# aircraft.net
KiCad netlist of a schematic drawn in Altium Designer
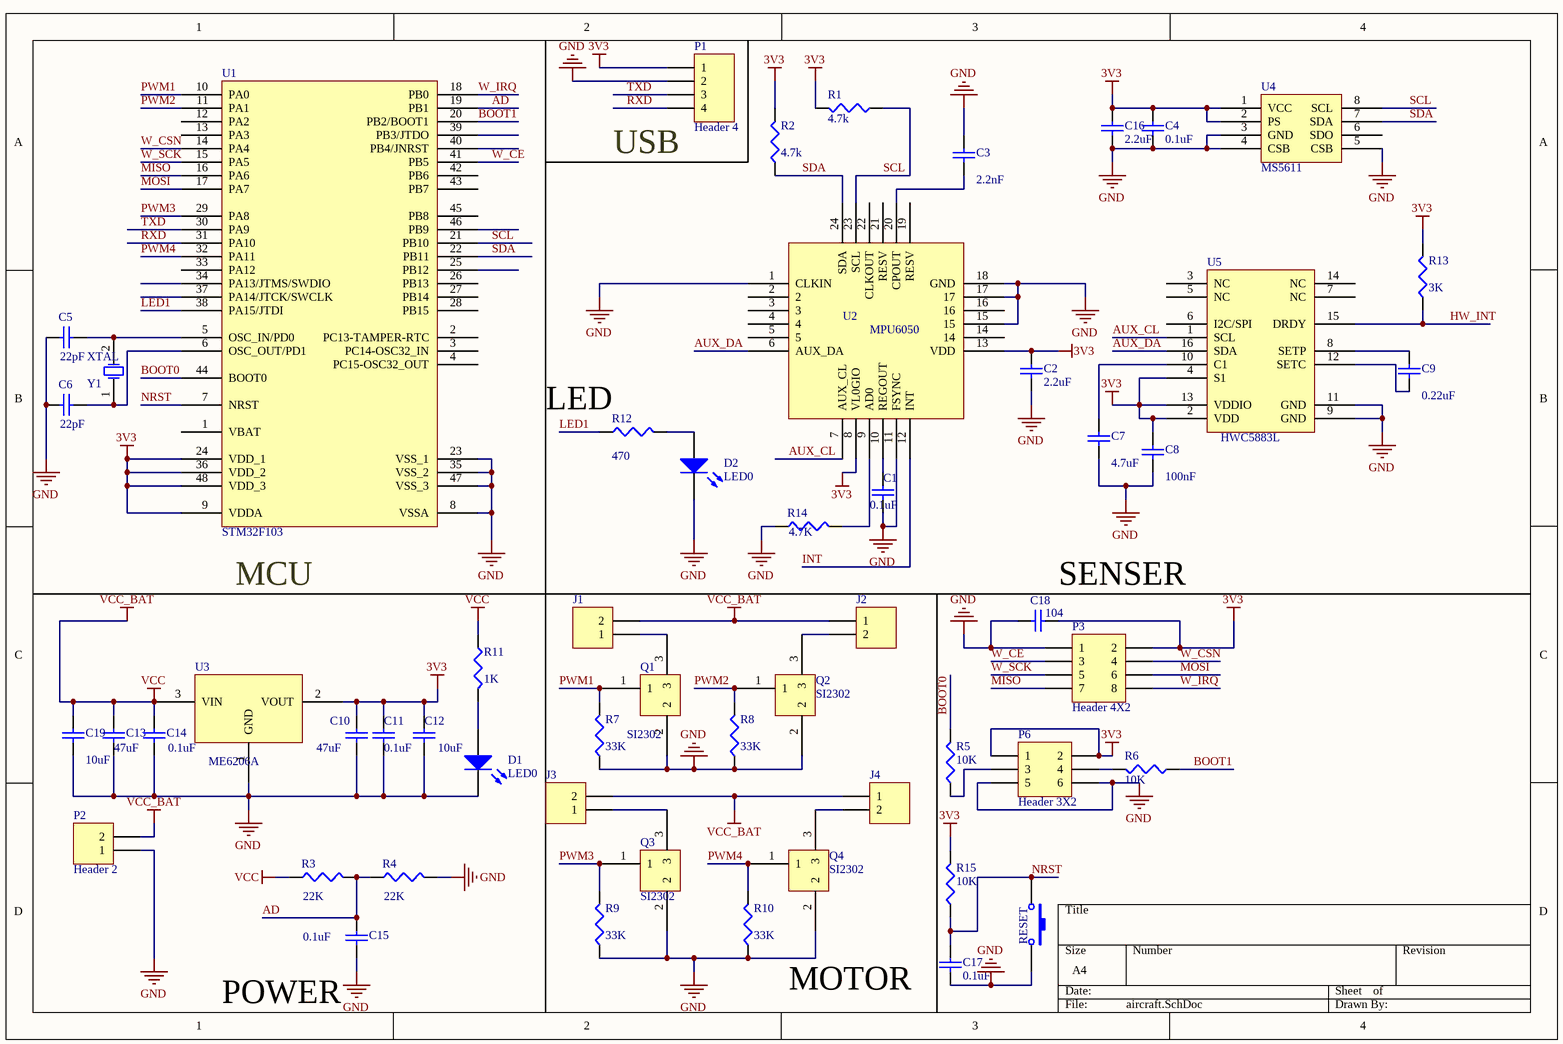
[diagram p0: aircraft.SchDoc]

(export (version "E")
  (design (tool "Eeschema 10.0.6"))
  (components
    (comp (ref "C1")
      (value "0.1uF")
      (footprint "0402")
      (description "Capacitor")
      (fields (field (name "Comment") "Cap") (field (name "PUBLISHER") "Altium Limited"))
      (libsource (lib "Miscellaneous Devices") (part "Cap"))
    )
    (comp (ref "C2")
      (value "2.2uF")
      (footprint "0402")
      (description "Capacitor")
      (fields (field (name "Comment") "Cap") (field (name "PUBLISHER") "Altium Limited"))
      (libsource (lib "Miscellaneous Devices") (part "Cap"))
    )
    (comp (ref "C3")
      (value "2.2nF")
      (footprint "0402")
      (description "Capacitor")
      (fields (field (name "Comment") "Cap") (field (name "PUBLISHER") "Altium Limited"))
      (libsource (lib "Miscellaneous Devices") (part "Cap"))
    )
    (comp (ref "C4")
      (value "0.1uF")
      (footprint "0402")
      (description "Capacitor")
      (fields (field (name "Comment") "Cap") (field (name "PUBLISHER") "Altium Limited"))
      (libsource (lib "Miscellaneous Devices") (part "Cap"))
    )
    (comp (ref "C5")
      (value "22pF")
      (footprint "0402")
      (description "Capacitor")
      (fields (field (name "Comment") "Cap") (field (name "PUBLISHER") "Altium Limited"))
      (libsource (lib "Miscellaneous Devices") (part "Cap"))
    )
    (comp (ref "C6")
      (value "22pF")
      (footprint "0402")
      (description "Capacitor")
      (fields (field (name "Comment") "Cap") (field (name "PUBLISHER") "Altium Limited"))
      (libsource (lib "Miscellaneous Devices") (part "Cap"))
    )
    (comp (ref "C7")
      (value "4.7uF")
      (footprint "0402")
      (description "Capacitor")
      (fields (field (name "Comment") "Cap") (field (name "PUBLISHER") "Altium Limited"))
      (libsource (lib "Miscellaneous Devices") (part "Cap"))
    )
    (comp (ref "C8")
      (value "100nF")
      (footprint "0402")
      (description "Capacitor")
      (fields (field (name "Comment") "Cap") (field (name "PUBLISHER") "Altium Limited"))
      (libsource (lib "Miscellaneous Devices") (part "Cap"))
    )
    (comp (ref "C9")
      (value "0.22uF")
      (footprint "0402")
      (description "Capacitor")
      (fields (field (name "Comment") "Cap") (field (name "PUBLISHER") "Altium Limited"))
      (libsource (lib "Miscellaneous Devices") (part "Cap"))
    )
    (comp (ref "C10")
      (value "47uF")
      (footprint "6-0805_L")
      (description "Capacitor")
      (fields (field (name "Comment") "Cap") (field (name "PUBLISHER") "Altium Limited"))
      (libsource (lib "Miscellaneous Devices") (part "Cap"))
    )
    (comp (ref "C11")
      (value "0.1uF")
      (footprint "0402")
      (description "Capacitor")
      (fields (field (name "Comment") "Cap") (field (name "PUBLISHER") "Altium Limited"))
      (libsource (lib "Miscellaneous Devices") (part "Cap"))
    )
    (comp (ref "C12")
      (value "10uF")
      (footprint "1608[0603]")
      (description "Capacitor")
      (fields (field (name "Comment") "Cap") (field (name "PUBLISHER") "Altium Limited"))
      (libsource (lib "Miscellaneous Devices") (part "Cap"))
    )
    (comp (ref "C13")
      (value "47uF")
      (footprint "6-0805_L")
      (description "Capacitor")
      (fields (field (name "Comment") "Cap") (field (name "PUBLISHER") "Altium Limited"))
      (libsource (lib "Miscellaneous Devices") (part "Cap"))
    )
    (comp (ref "C14")
      (value "0.1uF")
      (footprint "0402")
      (description "Capacitor")
      (fields (field (name "Comment") "Cap") (field (name "PUBLISHER") "Altium Limited"))
      (libsource (lib "Miscellaneous Devices") (part "Cap"))
    )
    (comp (ref "C15")
      (value "0.1uF")
      (footprint "0402")
      (description "Capacitor")
      (fields (field (name "Comment") "Cap") (field (name "PUBLISHER") "Altium Limited"))
      (libsource (lib "Miscellaneous Devices") (part "Cap"))
    )
    (comp (ref "C16")
      (value "2.2uF")
      (footprint "0402")
      (description "Capacitor")
      (fields (field (name "Comment") "Cap") (field (name "PUBLISHER") "Altium Limited"))
      (libsource (lib "Miscellaneous Devices") (part "Cap"))
    )
    (comp (ref "C17")
      (value "0.1uF")
      (footprint "0402")
      (description "Capacitor")
      (fields (field (name "Comment") "Cap") (field (name "PUBLISHER") "Altium Limited"))
      (libsource (lib "Miscellaneous Devices") (part "Cap"))
    )
    (comp (ref "C18")
      (value "104")
      (footprint "0402")
      (description "Capacitor")
      (fields (field (name "Comment") "Cap") (field (name "PUBLISHER") "Altium Limited"))
      (libsource (lib "Miscellaneous Devices") (part "Cap"))
    )
    (comp (ref "C19")
      (value "10uF")
      (footprint "1608[0603]")
      (description "Capacitor")
      (fields (field (name "Comment") "Cap") (field (name "PUBLISHER") "Altium Limited"))
      (libsource (lib "Miscellaneous Devices") (part "Cap"))
    )
    (comp (ref "D1")
      (value "LED0")
      (footprint "1608[0603]")
      (description "Typical INFRARED GaAs LED")
      (fields (field (name "PUBLISHER") "Altium Limited"))
      (libsource (lib "Miscellaneous Devices") (part "LED0"))
    )
    (comp (ref "D2")
      (value "LED0")
      (footprint "1608[0603]")
      (description "Typical INFRARED GaAs LED")
      (fields (field (name "PUBLISHER") "Altium Limited"))
      (libsource (lib "Miscellaneous Devices") (part "LED0"))
    )
    (comp (ref "J1")
      (value "Header 2")
      (footprint "HDR1X2")
      (description "Header, 2-Pin")
      (fields (field (name "PUBLISHER") "Altium Limited"))
      (libsource (lib "Miscellaneous Connectors") (part "Header 2"))
    )
    (comp (ref "J2")
      (value "Header 2")
      (footprint "HDR1X2")
      (description "Header, 2-Pin")
      (fields (field (name "PUBLISHER") "Altium Limited"))
      (libsource (lib "") (part "Header 2_1"))
    )
    (comp (ref "J3")
      (value "Header 2")
      (footprint "HDR1X2")
      (description "Header, 2-Pin")
      (fields (field (name "PUBLISHER") "Altium Limited"))
      (libsource (lib "Miscellaneous Connectors") (part "Header 2"))
    )
    (comp (ref "J4")
      (value "Header 2")
      (footprint "HDR1X2")
      (description "Header, 2-Pin")
      (fields (field (name "PUBLISHER") "Altium Limited"))
      (libsource (lib "") (part "Header 2_1"))
    )
    (comp (ref "P1")
      (value "Header 4")
      (footprint "HDR1X4")
      (description "Header, 4-Pin")
      (fields (field (name "PUBLISHER") "Altium Limited"))
      (libsource (lib "Miscellaneous Connectors") (part "Header 4"))
    )
    (comp (ref "P2")
      (value "Header 2")
      (footprint "HDR1X2")
      (description "Header, 2-Pin")
      (fields (field (name "PUBLISHER") "Altium Limited"))
      (libsource (lib "Miscellaneous Connectors") (part "Header 2"))
    )
    (comp (ref "P3")
      (value "Header 4X2")
      (footprint "HDR2X4")
      (description "Header, 4-Pin, Dual row")
      (fields (field (name "PUBLISHER") "Altium Limited"))
      (libsource (lib "Miscellaneous Connectors") (part "Header 4X2"))
    )
    (comp (ref "P6")
      (value "Header 3X2")
      (footprint "HDR2X3")
      (description "Header, 3-Pin, Dual row")
      (fields (field (name "PUBLISHER") "Altium Limited"))
      (libsource (lib "Miscellaneous Connectors") (part "Header 3X2"))
    )
    (comp (ref "Q1")
      (value "SI2302")
      (footprint "SOT-23_M")
      (libsource (lib "aircraftschlib") (part "SI2302"))
    )
    (comp (ref "Q2")
      (value "SI2302")
      (footprint "SOT-23_M")
      (libsource (lib "aircraftschlib") (part "SI2302"))
    )
    (comp (ref "Q3")
      (value "SI2302")
      (footprint "SOT-23_M")
      (libsource (lib "aircraftschlib") (part "SI2302"))
    )
    (comp (ref "Q4")
      (value "SI2302")
      (footprint "SOT-23_M")
      (libsource (lib "aircraftschlib") (part "SI2302"))
    )
    (comp (ref "R1")
      (value "4.7k")
      (footprint "0402")
      (description "Resistor")
      (fields (field (name "Comment") "Res3") (field (name "PUBLISHER") "Altium Limited"))
      (libsource (lib "Miscellaneous Devices") (part "Res3"))
    )
    (comp (ref "R2")
      (value "4.7k")
      (footprint "0402")
      (description "Resistor")
      (fields (field (name "Comment") "Res3") (field (name "PUBLISHER") "Altium Limited"))
      (libsource (lib "Miscellaneous Devices") (part "Res3"))
    )
    (comp (ref "R3")
      (value "22K")
      (footprint "0402")
      (description "Resistor")
      (fields (field (name "Comment") "Res3") (field (name "PUBLISHER") "Altium Limited"))
      (libsource (lib "Miscellaneous Devices") (part "Res3"))
    )
    (comp (ref "R4")
      (value "22K")
      (footprint "0402")
      (description "Resistor")
      (fields (field (name "Comment") "Res3") (field (name "PUBLISHER") "Altium Limited"))
      (libsource (lib "Miscellaneous Devices") (part "Res3"))
    )
    (comp (ref "R5")
      (value "10K")
      (footprint "0402")
      (description "Resistor")
      (fields (field (name "Comment") "Res3") (field (name "PUBLISHER") "Altium Limited"))
      (libsource (lib "Miscellaneous Devices") (part "Res3"))
    )
    (comp (ref "R6")
      (value "10K")
      (footprint "0402")
      (description "Resistor")
      (fields (field (name "Comment") "Res3") (field (name "PUBLISHER") "Altium Limited"))
      (libsource (lib "Miscellaneous Devices") (part "Res3"))
    )
    (comp (ref "R7")
      (value "33K")
      (footprint "0402")
      (description "Resistor")
      (fields (field (name "Comment") "Res3") (field (name "PUBLISHER") "Altium Limited"))
      (libsource (lib "Miscellaneous Devices") (part "Res3"))
    )
    (comp (ref "R8")
      (value "33K")
      (footprint "0402")
      (description "Resistor")
      (fields (field (name "Comment") "Res3") (field (name "PUBLISHER") "Altium Limited"))
      (libsource (lib "Miscellaneous Devices") (part "Res3"))
    )
    (comp (ref "R9")
      (value "33K")
      (footprint "0402")
      (description "Resistor")
      (fields (field (name "Comment") "Res3") (field (name "PUBLISHER") "Altium Limited"))
      (libsource (lib "Miscellaneous Devices") (part "Res3"))
    )
    (comp (ref "R10")
      (value "33K")
      (footprint "0402")
      (description "Resistor")
      (fields (field (name "Comment") "Res3") (field (name "PUBLISHER") "Altium Limited"))
      (libsource (lib "Miscellaneous Devices") (part "Res3"))
    )
    (comp (ref "R11")
      (value "1K")
      (footprint "0402")
      (description "Resistor")
      (fields (field (name "Comment") "Res3") (field (name "PUBLISHER") "Altium Limited"))
      (libsource (lib "Miscellaneous Devices") (part "Res3"))
    )
    (comp (ref "R12")
      (value "470")
      (footprint "0402")
      (description "Resistor")
      (fields (field (name "Comment") "Res3") (field (name "PUBLISHER") "Altium Limited"))
      (libsource (lib "Miscellaneous Devices") (part "Res3"))
    )
    (comp (ref "R13")
      (value "3K")
      (footprint "0402")
      (description "Resistor")
      (fields (field (name "Comment") "Res3") (field (name "PUBLISHER") "Altium Limited"))
      (libsource (lib "Miscellaneous Devices") (part "Res3"))
    )
    (comp (ref "R14")
      (value "4.7K")
      (footprint "0402")
      (description "Resistor")
      (fields (field (name "Comment") "Res3") (field (name "PUBLISHER") "Altium Limited"))
      (libsource (lib "Miscellaneous Devices") (part "Res3"))
    )
    (comp (ref "R15")
      (value "10K")
      (footprint "0402")
      (description "Resistor")
      (fields (field (name "Comment") "Res3") (field (name "PUBLISHER") "Altium Limited"))
      (libsource (lib "Miscellaneous Devices") (part "Res3"))
    )
    (comp (ref "RESET")
      (value "SW-PB")
      (footprint "SW2")
      (description "Switch")
      (fields (field (name "PUBLISHER") "Altium Limited"))
      (libsource (lib "Miscellaneous Devices") (part "SW-PB"))
    )
    (comp (ref "U1")
      (value "STM32F103")
      (footprint "LQFP48S")
      (libsource (lib "aircraftschlib") (part "STM32F103"))
    )
    (comp (ref "U2")
      (value "MPU6050")
      (footprint "QFN24")
      (libsource (lib "aircraftschlib") (part "MPU6050"))
    )
    (comp (ref "U3")
      (value "ME6206A")
      (footprint "SOT23_M")
      (libsource (lib "aircraftschlib") (part "ME6206A"))
    )
    (comp (ref "U4")
      (value "MS5611")
      (footprint "MS5611 - duplicate")
      (libsource (lib "aircraftschlib") (part "MS5611"))
    )
    (comp (ref "U5")
      (value "HWC5883L")
      (footprint "HMC5883L")
      (libsource (lib "aircraftschlib") (part "HMC5883L"))
    )
    (comp (ref "Y1")
      (value "XTAL")
      (footprint "XTAL2")
      (description "Crystal Oscillator")
      (fields (field (name "PUBLISHER") "Altium Limited"))
      (libsource (lib "Miscellaneous Devices") (part "XTAL"))
    )
  )
  (nets
    (net (code "1") (name "/AD") (class "Default")
      (node (ref "C15") (pin "2") (pinfunction "2_2") (pintype "passive"))
      (node (ref "R3") (pin "2") (pinfunction "2_2") (pintype "passive"))
      (node (ref "R4") (pin "1") (pinfunction "1_1") (pintype "passive"))
      (node (ref "U1") (pin "19") (pinfunction "PB1_19") (pintype "passive"))
    )
    (net (code "2") (name "/AUX_CL") (class "Default")
      (node (ref "U2") (pin "7") (pinfunction "AUX_CL_7") (pintype "passive"))
      (node (ref "U5") (pin "1") (pinfunction "SCL_1") (pintype "passive"))
    )
    (net (code "3") (name "/AUX_DA") (class "Default")
      (node (ref "U2") (pin "6") (pinfunction "AUX_DA_6") (pintype "passive"))
      (node (ref "U5") (pin "16") (pinfunction "SDA_16") (pintype "passive"))
    )
    (net (code "4") (name "/BOOT0") (class "Default")
      (node (ref "R5") (pin "2") (pinfunction "2_2") (pintype "passive"))
      (node (ref "U1") (pin "44") (pinfunction "BOOT0_44") (pintype "passive"))
    )
    (net (code "5") (name "/BOOT1") (class "Default")
      (node (ref "R6") (pin "1") (pinfunction "1_1") (pintype "passive"))
      (node (ref "U1") (pin "20") (pinfunction "PB2/BOOT1_20") (pintype "passive"))
    )
    (net (code "6") (name "/HW_INT") (class "Default")
      (node (ref "R13") (pin "1") (pinfunction "1_1") (pintype "passive"))
      (node (ref "U5") (pin "15") (pinfunction "DRDY_15") (pintype "passive"))
    )
    (net (code "7") (name "/INT") (class "Default")
      (node (ref "U2") (pin "12") (pinfunction "INT_12") (pintype "passive"))
    )
    (net (code "8") (name "/LED1") (class "Default")
      (node (ref "R12") (pin "1") (pinfunction "1_1") (pintype "passive"))
      (node (ref "U1") (pin "38") (pinfunction "PA15/JTDI_38") (pintype "passive"))
    )
    (net (code "9") (name "/MISO") (class "Default")
      (node (ref "P3") (pin "7") (pinfunction "7_7") (pintype "passive"))
      (node (ref "U1") (pin "16") (pinfunction "PA6_16") (pintype "passive"))
    )
    (net (code "10") (name "/MOSI") (class "Default")
      (node (ref "P3") (pin "6") (pinfunction "6_6") (pintype "passive"))
      (node (ref "U1") (pin "17") (pinfunction "PA7_17") (pintype "passive"))
    )
    (net (code "11") (name "/NRST") (class "Default")
      (node (ref "C17") (pin "1") (pinfunction "1_1") (pintype "passive"))
      (node (ref "R15") (pin "1") (pinfunction "1_1") (pintype "passive"))
      (node (ref "RESET") (pin "1") (pinfunction "1_1") (pintype "passive"))
      (node (ref "U1") (pin "7") (pinfunction "NRST_7") (pintype "passive"))
    )
    (net (code "12") (name "/PWM1") (class "Default")
      (node (ref "Q1") (pin "1") (pinfunction "1_1") (pintype "passive"))
      (node (ref "R7") (pin "2") (pinfunction "2_2") (pintype "passive"))
      (node (ref "U1") (pin "10") (pinfunction "PA0_10") (pintype "passive"))
    )
    (net (code "13") (name "/PWM2") (class "Default")
      (node (ref "Q2") (pin "1") (pinfunction "1_1") (pintype "passive"))
      (node (ref "R8") (pin "2") (pinfunction "2_2") (pintype "passive"))
      (node (ref "U1") (pin "11") (pinfunction "PA1_11") (pintype "passive"))
    )
    (net (code "14") (name "/PWM3") (class "Default")
      (node (ref "Q3") (pin "1") (pinfunction "1_1") (pintype "passive"))
      (node (ref "R9") (pin "2") (pinfunction "2_2") (pintype "passive"))
      (node (ref "U1") (pin "29") (pinfunction "PA8_29") (pintype "passive"))
    )
    (net (code "15") (name "/PWM4") (class "Default")
      (node (ref "Q4") (pin "1") (pinfunction "1_1") (pintype "passive"))
      (node (ref "R10") (pin "2") (pinfunction "2_2") (pintype "passive"))
      (node (ref "U1") (pin "32") (pinfunction "PA11_32") (pintype "passive"))
    )
    (net (code "16") (name "/RXD") (class "Default")
      (node (ref "P1") (pin "4") (pinfunction "4_4") (pintype "passive"))
      (node (ref "U1") (pin "31") (pinfunction "PA10_31") (pintype "passive"))
    )
    (net (code "17") (name "/SCL") (class "Default")
      (node (ref "R1") (pin "1") (pinfunction "1_1") (pintype "passive"))
      (node (ref "U1") (pin "21") (pinfunction "PB10_21") (pintype "passive"))
      (node (ref "U2") (pin "23") (pinfunction "SCL_23") (pintype "passive"))
      (node (ref "U4") (pin "8") (pinfunction "SCL_8") (pintype "passive"))
    )
    (net (code "18") (name "/SDA") (class "Default")
      (node (ref "R2") (pin "1") (pinfunction "1_1") (pintype "passive"))
      (node (ref "U1") (pin "22") (pinfunction "PB11_22") (pintype "passive"))
      (node (ref "U2") (pin "24") (pinfunction "SDA_24") (pintype "passive"))
      (node (ref "U4") (pin "7") (pinfunction "SDA_7") (pintype "passive"))
    )
    (net (code "19") (name "/TXD") (class "Default")
      (node (ref "P1") (pin "3") (pinfunction "3_3") (pintype "passive"))
      (node (ref "U1") (pin "30") (pinfunction "PA9_30") (pintype "passive"))
    )
    (net (code "20") (name "/W_CE") (class "Default")
      (node (ref "P3") (pin "3") (pinfunction "3_3") (pintype "passive"))
      (node (ref "U1") (pin "41") (pinfunction "PB5_41") (pintype "passive"))
    )
    (net (code "21") (name "/W_CSN") (class "Default")
      (node (ref "P3") (pin "4") (pinfunction "4_4") (pintype "passive"))
      (node (ref "U1") (pin "14") (pinfunction "PA4_14") (pintype "passive"))
    )
    (net (code "22") (name "/W_IRQ") (class "Default")
      (node (ref "P3") (pin "8") (pinfunction "8_8") (pintype "passive"))
      (node (ref "U1") (pin "18") (pinfunction "PB0_18") (pintype "passive"))
    )
    (net (code "23") (name "/W_SCK") (class "Default")
      (node (ref "P3") (pin "5") (pinfunction "5_5") (pintype "passive"))
      (node (ref "U1") (pin "15") (pinfunction "PA5_15") (pintype "passive"))
    )
    (net (code "24") (name "3V3") (class "Default")
      (node (ref "C10") (pin "2") (pinfunction "2_2") (pintype "passive"))
      (node (ref "C11") (pin "1") (pinfunction "1_1") (pintype "passive"))
      (node (ref "C12") (pin "1") (pinfunction "1_1") (pintype "passive"))
      (node (ref "C16") (pin "2") (pinfunction "2_2") (pintype "passive"))
      (node (ref "C18") (pin "2") (pinfunction "2_2") (pintype "passive"))
      (node (ref "C2") (pin "2") (pinfunction "2_2") (pintype "passive"))
      (node (ref "C4") (pin "2") (pinfunction "2_2") (pintype "passive"))
      (node (ref "C8") (pin "2") (pinfunction "2_2") (pintype "passive"))
      (node (ref "P1") (pin "1") (pinfunction "1_1") (pintype "passive"))
      (node (ref "P3") (pin "2") (pinfunction "2_2") (pintype "passive"))
      (node (ref "P6") (pin "1") (pinfunction "1_1") (pintype "passive"))
      (node (ref "P6") (pin "2") (pinfunction "2_2") (pintype "passive"))
      (node (ref "R1") (pin "2") (pinfunction "2_2") (pintype "passive"))
      (node (ref "R13") (pin "2") (pinfunction "2_2") (pintype "passive"))
      (node (ref "R15") (pin "2") (pinfunction "2_2") (pintype "passive"))
      (node (ref "R2") (pin "2") (pinfunction "2_2") (pintype "passive"))
      (node (ref "U1") (pin "24") (pinfunction "VDD_1_24") (pintype "passive"))
      (node (ref "U1") (pin "36") (pinfunction "VDD_2_36") (pintype "passive"))
      (node (ref "U1") (pin "48") (pinfunction "VDD_3_48") (pintype "passive"))
      (node (ref "U1") (pin "9") (pinfunction "VDDA_9") (pintype "passive"))
      (node (ref "U2") (pin "13") (pinfunction "VDD_13") (pintype "passive"))
      (node (ref "U2") (pin "8") (pinfunction "VL0GIO_8") (pintype "passive"))
      (node (ref "U3") (pin "2") (pinfunction "VOUT_2") (pintype "passive"))
      (node (ref "U4") (pin "1") (pinfunction "VCC_1") (pintype "passive"))
      (node (ref "U4") (pin "2") (pinfunction "PS_2") (pintype "passive"))
      (node (ref "U5") (pin "13") (pinfunction "VDDIO_13") (pintype "passive"))
      (node (ref "U5") (pin "2") (pinfunction "VDD_2") (pintype "passive"))
      (node (ref "U5") (pin "4") (pinfunction "S1_4") (pintype "passive"))
    )
    (net (code "25") (name "GND") (class "Default")
      (node (ref "C1") (pin "1") (pinfunction "1_1") (pintype "passive"))
      (node (ref "C10") (pin "1") (pinfunction "1_1") (pintype "passive"))
      (node (ref "C11") (pin "2") (pinfunction "2_2") (pintype "passive"))
      (node (ref "C12") (pin "2") (pinfunction "2_2") (pintype "passive"))
      (node (ref "C13") (pin "1") (pinfunction "1_1") (pintype "passive"))
      (node (ref "C14") (pin "1") (pinfunction "1_1") (pintype "passive"))
      (node (ref "C15") (pin "1") (pinfunction "1_1") (pintype "passive"))
      (node (ref "C16") (pin "1") (pinfunction "1_1") (pintype "passive"))
      (node (ref "C17") (pin "2") (pinfunction "2_2") (pintype "passive"))
      (node (ref "C18") (pin "1") (pinfunction "1_1") (pintype "passive"))
      (node (ref "C19") (pin "1") (pinfunction "1_1") (pintype "passive"))
      (node (ref "C2") (pin "1") (pinfunction "1_1") (pintype "passive"))
      (node (ref "C3") (pin "2") (pinfunction "2_2") (pintype "passive"))
      (node (ref "C4") (pin "1") (pinfunction "1_1") (pintype "passive"))
      (node (ref "C5") (pin "1") (pinfunction "1_1") (pintype "passive"))
      (node (ref "C6") (pin "1") (pinfunction "1_1") (pintype "passive"))
      (node (ref "C7") (pin "1") (pinfunction "1_1") (pintype "passive"))
      (node (ref "C8") (pin "1") (pinfunction "1_1") (pintype "passive"))
      (node (ref "D1") (pin "2") (pinfunction "K_2") (pintype "passive"))
      (node (ref "D2") (pin "2") (pinfunction "K_2") (pintype "passive"))
      (node (ref "P1") (pin "2") (pinfunction "2_2") (pintype "passive"))
      (node (ref "P2") (pin "1") (pinfunction "1_1") (pintype "passive"))
      (node (ref "P3") (pin "1") (pinfunction "1_1") (pintype "passive"))
      (node (ref "P6") (pin "5") (pinfunction "5_5") (pintype "passive"))
      (node (ref "P6") (pin "6") (pinfunction "6_6") (pintype "passive"))
      (node (ref "Q1") (pin "2") (pinfunction "2_2") (pintype "passive"))
      (node (ref "Q2") (pin "2") (pinfunction "2_2") (pintype "passive"))
      (node (ref "Q3") (pin "2") (pinfunction "2_2") (pintype "passive"))
      (node (ref "Q4") (pin "2") (pinfunction "2_2") (pintype "passive"))
      (node (ref "R10") (pin "1") (pinfunction "1_1") (pintype "passive"))
      (node (ref "R14") (pin "1") (pinfunction "1_1") (pintype "passive"))
      (node (ref "R4") (pin "2") (pinfunction "2_2") (pintype "passive"))
      (node (ref "R7") (pin "1") (pinfunction "1_1") (pintype "passive"))
      (node (ref "R8") (pin "1") (pinfunction "1_1") (pintype "passive"))
      (node (ref "R9") (pin "1") (pinfunction "1_1") (pintype "passive"))
      (node (ref "RESET") (pin "2") (pinfunction "2_2") (pintype "passive"))
      (node (ref "U1") (pin "23") (pinfunction "VSS_1_23") (pintype "passive"))
      (node (ref "U1") (pin "35") (pinfunction "VSS_2_35") (pintype "passive"))
      (node (ref "U1") (pin "47") (pinfunction "VSS_3_47") (pintype "passive"))
      (node (ref "U1") (pin "8") (pinfunction "VSSA_8") (pintype "passive"))
      (node (ref "U2") (pin "1") (pinfunction "CLKIN_1") (pintype "passive"))
      (node (ref "U2") (pin "11") (pinfunction "FSYNC_11") (pintype "passive"))
      (node (ref "U2") (pin "15") (pinfunction "15_15") (pintype "passive"))
      (node (ref "U2") (pin "17") (pinfunction "17_17") (pintype "passive"))
      (node (ref "U2") (pin "18") (pinfunction "GND_18") (pintype "passive"))
      (node (ref "U3") (pin "1") (pinfunction "GND_1") (pintype "passive"))
      (node (ref "U4") (pin "3") (pinfunction "GND_3") (pintype "passive"))
      (node (ref "U4") (pin "4") (pinfunction "CSB_4") (pintype "passive"))
      (node (ref "U4") (pin "5") (pinfunction "CSB_5") (pintype "passive"))
      (node (ref "U5") (pin "11") (pinfunction "GND_11") (pintype "passive"))
      (node (ref "U5") (pin "9") (pinfunction "GND_9") (pintype "passive"))
    )
    (net (code "26") (name "Net-(D1-A)") (class "Default")
      (node (ref "D1") (pin "1") (pinfunction "A_1") (pintype "passive"))
      (node (ref "R11") (pin "2") (pinfunction "2_2") (pintype "passive"))
    )
    (net (code "27") (name "Net-(D2-A)") (class "Default")
      (node (ref "D2") (pin "1") (pinfunction "A_1") (pintype "passive"))
      (node (ref "R12") (pin "2") (pinfunction "2_2") (pintype "passive"))
    )
    (net (code "28") (name "Net-(J1-Pad1)") (class "Default")
      (node (ref "J1") (pin "1") (pinfunction "1_1") (pintype "passive"))
      (node (ref "Q1") (pin "3") (pinfunction "3_3") (pintype "passive"))
    )
    (net (code "29") (name "Net-(J2-Pad2)") (class "Default")
      (node (ref "J2") (pin "2") (pinfunction "2_2") (pintype "passive"))
      (node (ref "Q2") (pin "3") (pinfunction "3_3") (pintype "passive"))
    )
    (net (code "30") (name "Net-(J3-Pad1)") (class "Default")
      (node (ref "J3") (pin "1") (pinfunction "1_1") (pintype "passive"))
      (node (ref "Q3") (pin "3") (pinfunction "3_3") (pintype "passive"))
    )
    (net (code "31") (name "Net-(J4-Pad2)") (class "Default")
      (node (ref "J4") (pin "2") (pinfunction "2_2") (pintype "passive"))
      (node (ref "Q4") (pin "3") (pinfunction "3_3") (pintype "passive"))
    )
    (net (code "32") (name "Net-(P6-Pad3)") (class "Default")
      (node (ref "P6") (pin "3") (pinfunction "3_3") (pintype "passive"))
      (node (ref "R5") (pin "1") (pinfunction "1_1") (pintype "passive"))
    )
    (net (code "33") (name "Net-(P6-Pad4)") (class "Default")
      (node (ref "P6") (pin "4") (pinfunction "4_4") (pintype "passive"))
      (node (ref "R6") (pin "2") (pinfunction "2_2") (pintype "passive"))
    )
    (net (code "34") (name "Net-(U1-OSC_IN{slash}PD0)") (class "Default")
      (node (ref "C5") (pin "2") (pinfunction "2_2") (pintype "passive"))
      (node (ref "U1") (pin "5") (pinfunction "OSC_IN/PD0_5") (pintype "passive"))
      (node (ref "Y1") (pin "2") (pinfunction "OSC2_2") (pintype "passive"))
    )
    (net (code "35") (name "Net-(U1-OSC_OUT{slash}PD1)") (class "Default")
      (node (ref "C6") (pin "2") (pinfunction "2_2") (pintype "passive"))
      (node (ref "U1") (pin "6") (pinfunction "OSC_OUT/PD1_6") (pintype "passive"))
      (node (ref "Y1") (pin "1") (pinfunction "OSC1_1") (pintype "passive"))
    )
    (net (code "36") (name "Net-(U2-AD0)") (class "Default")
      (node (ref "R14") (pin "2") (pinfunction "2_2") (pintype "passive"))
      (node (ref "U2") (pin "9") (pinfunction "AD0_9") (pintype "passive"))
    )
    (net (code "37") (name "Net-(U2-CPOUT)") (class "Default")
      (node (ref "C3") (pin "1") (pinfunction "1_1") (pintype "passive"))
      (node (ref "U2") (pin "20") (pinfunction "CPOUT_20") (pintype "passive"))
    )
    (net (code "38") (name "Net-(U2-REGOUT)") (class "Default")
      (node (ref "C1") (pin "2") (pinfunction "2_2") (pintype "passive"))
      (node (ref "U2") (pin "10") (pinfunction "REGOUT_10") (pintype "passive"))
    )
    (net (code "39") (name "Net-(U5-C1)") (class "Default")
      (node (ref "C7") (pin "2") (pinfunction "2_2") (pintype "passive"))
      (node (ref "U5") (pin "10") (pinfunction "C1_10") (pintype "passive"))
    )
    (net (code "40") (name "Net-(U5-SETC)") (class "Default")
      (node (ref "C9") (pin "1") (pinfunction "1_1") (pintype "passive"))
      (node (ref "U5") (pin "12") (pinfunction "SETC_12") (pintype "passive"))
    )
    (net (code "41") (name "Net-(U5-SETP)") (class "Default")
      (node (ref "C9") (pin "2") (pinfunction "2_2") (pintype "passive"))
      (node (ref "U5") (pin "8") (pinfunction "SETP_8") (pintype "passive"))
    )
    (net (code "42") (name "VCC") (class "Default")
      (node (ref "C13") (pin "2") (pinfunction "2_2") (pintype "passive"))
      (node (ref "C14") (pin "2") (pinfunction "2_2") (pintype "passive"))
      (node (ref "C19") (pin "2") (pinfunction "2_2") (pintype "passive"))
      (node (ref "J1") (pin "2") (pinfunction "2_2") (pintype "passive"))
      (node (ref "J2") (pin "1") (pinfunction "1_1") (pintype "passive"))
      (node (ref "J3") (pin "2") (pinfunction "2_2") (pintype "passive"))
      (node (ref "J4") (pin "1") (pinfunction "1_1") (pintype "passive"))
      (node (ref "P2") (pin "2") (pinfunction "2_2") (pintype "passive"))
      (node (ref "R11") (pin "1") (pinfunction "1_1") (pintype "passive"))
      (node (ref "R3") (pin "1") (pinfunction "1_1") (pintype "passive"))
      (node (ref "U3") (pin "3") (pinfunction "VIN_3") (pintype "passive"))
    )
    (net (code "43") (name "unconnected-(U1-PA2-Pad12)") (class "Default")
      (node (ref "U1") (pin "12") (pinfunction "PA2_12") (pintype "passive"))
    )
    (net (code "44") (name "unconnected-(U1-PA3-Pad13)") (class "Default")
      (node (ref "U1") (pin "13") (pinfunction "PA3_13") (pintype "passive"))
    )
    (net (code "45") (name "unconnected-(U1-PA12-Pad33)") (class "Default")
      (node (ref "U1") (pin "33") (pinfunction "PA12_33") (pintype "passive"))
    )
    (net (code "46") (name "unconnected-(U1-PA13{slash}JTMS{slash}SWDIO-Pad34)") (class "Default")
      (node (ref "U1") (pin "34") (pinfunction "PA13/JTMS/SWDIO_34") (pintype "passive"))
    )
    (net (code "47") (name "unconnected-(U1-PA14{slash}JTCK{slash}SWCLK-Pad37)") (class "Default")
      (node (ref "U1") (pin "37") (pinfunction "PA14/JTCK/SWCLK_37") (pintype "passive"))
    )
    (net (code "48") (name "unconnected-(U1-PB3{slash}JTDO-Pad39)") (class "Default")
      (node (ref "U1") (pin "39") (pinfunction "PB3/JTDO_39") (pintype "passive"))
    )
    (net (code "49") (name "unconnected-(U1-PB4{slash}JNRST-Pad40)") (class "Default")
      (node (ref "U1") (pin "40") (pinfunction "PB4/JNRST_40") (pintype "passive"))
    )
    (net (code "50") (name "unconnected-(U1-PB6-Pad42)") (class "Default")
      (node (ref "U1") (pin "42") (pinfunction "PB6_42") (pintype "passive"))
    )
    (net (code "51") (name "unconnected-(U1-PB7-Pad43)") (class "Default")
      (node (ref "U1") (pin "43") (pinfunction "PB7_43") (pintype "passive"))
    )
    (net (code "52") (name "unconnected-(U1-PB8-Pad45)") (class "Default")
      (node (ref "U1") (pin "45") (pinfunction "PB8_45") (pintype "passive"))
    )
    (net (code "53") (name "unconnected-(U1-PB9-Pad46)") (class "Default")
      (node (ref "U1") (pin "46") (pinfunction "PB9_46") (pintype "passive"))
    )
    (net (code "54") (name "unconnected-(U1-PB12-Pad25)") (class "Default")
      (node (ref "U1") (pin "25") (pinfunction "PB12_25") (pintype "passive"))
    )
    (net (code "55") (name "unconnected-(U1-PB13-Pad26)") (class "Default")
      (node (ref "U1") (pin "26") (pinfunction "PB13_26") (pintype "passive"))
    )
    (net (code "56") (name "unconnected-(U1-PB14-Pad27)") (class "Default")
      (node (ref "U1") (pin "27") (pinfunction "PB14_27") (pintype "passive"))
    )
    (net (code "57") (name "unconnected-(U1-PB15-Pad28)") (class "Default")
      (node (ref "U1") (pin "28") (pinfunction "PB15_28") (pintype "passive"))
    )
    (net (code "58") (name "unconnected-(U1-PC13-TAMPER-RTC-Pad2)") (class "Default")
      (node (ref "U1") (pin "2") (pinfunction "PC13-TAMPER-RTC_2") (pintype "passive"))
    )
    (net (code "59") (name "unconnected-(U1-PC14-OSC32_IN-Pad3)") (class "Default")
      (node (ref "U1") (pin "3") (pinfunction "PC14-OSC32_IN_3") (pintype "passive"))
    )
    (net (code "60") (name "unconnected-(U1-PC15-OSC32_OUT-Pad4)") (class "Default")
      (node (ref "U1") (pin "4") (pinfunction "PC15-OSC32_OUT_4") (pintype "passive"))
    )
    (net (code "61") (name "unconnected-(U1-VBAT-Pad1)") (class "Default")
      (node (ref "U1") (pin "1") (pinfunction "VBAT_1") (pintype "passive"))
    )
    (net (code "62") (name "unconnected-(U2-CLKOUT-Pad22)") (class "Default")
      (node (ref "U2") (pin "22") (pinfunction "CLKOUT_22") (pintype "passive"))
    )
    (net (code "63") (name "unconnected-(U2-Pad2)") (class "Default")
      (node (ref "U2") (pin "2") (pinfunction "2_2") (pintype "passive"))
    )
    (net (code "64") (name "unconnected-(U2-Pad3)") (class "Default")
      (node (ref "U2") (pin "3") (pinfunction "3_3") (pintype "passive"))
    )
    (net (code "65") (name "unconnected-(U2-Pad4)") (class "Default")
      (node (ref "U2") (pin "4") (pinfunction "4_4") (pintype "passive"))
    )
    (net (code "66") (name "unconnected-(U2-Pad5)") (class "Default")
      (node (ref "U2") (pin "5") (pinfunction "5_5") (pintype "passive"))
    )
    (net (code "67") (name "unconnected-(U2-Pad14)") (class "Default")
      (node (ref "U2") (pin "14") (pinfunction "14_14") (pintype "passive"))
    )
    (net (code "68") (name "unconnected-(U2-Pad16)") (class "Default")
      (node (ref "U2") (pin "16") (pinfunction "16_16") (pintype "passive"))
    )
    (net (code "69") (name "unconnected-(U2-RESV-Pad19)") (class "Default")
      (node (ref "U2") (pin "19") (pinfunction "RESV_19") (pintype "passive"))
    )
    (net (code "70") (name "unconnected-(U2-RESV-Pad21)") (class "Default")
      (node (ref "U2") (pin "21") (pinfunction "RESV_21") (pintype "passive"))
    )
    (net (code "71") (name "unconnected-(U4-SDO-Pad6)") (class "Default")
      (node (ref "U4") (pin "6") (pinfunction "SDO_6") (pintype "passive"))
    )
    (net (code "72") (name "unconnected-(U5-I2C{slash}SPI-Pad6)") (class "Default")
      (node (ref "U5") (pin "6") (pinfunction "I2C/SPI_6") (pintype "passive"))
    )
    (net (code "73") (name "unconnected-(U5-NC-Pad3)") (class "Default")
      (node (ref "U5") (pin "3") (pinfunction "NC_3") (pintype "passive"))
    )
    (net (code "74") (name "unconnected-(U5-NC-Pad5)") (class "Default")
      (node (ref "U5") (pin "5") (pinfunction "NC_5") (pintype "passive"))
    )
    (net (code "75") (name "unconnected-(U5-NC-Pad7)") (class "Default")
      (node (ref "U5") (pin "7") (pinfunction "NC_7") (pintype "passive"))
    )
    (net (code "76") (name "unconnected-(U5-NC-Pad14)") (class "Default")
      (node (ref "U5") (pin "14") (pinfunction "NC_14") (pintype "passive"))
    )
  )
)
